# MCU.net
KiCad netlist of a schematic drawn in Altium Designer
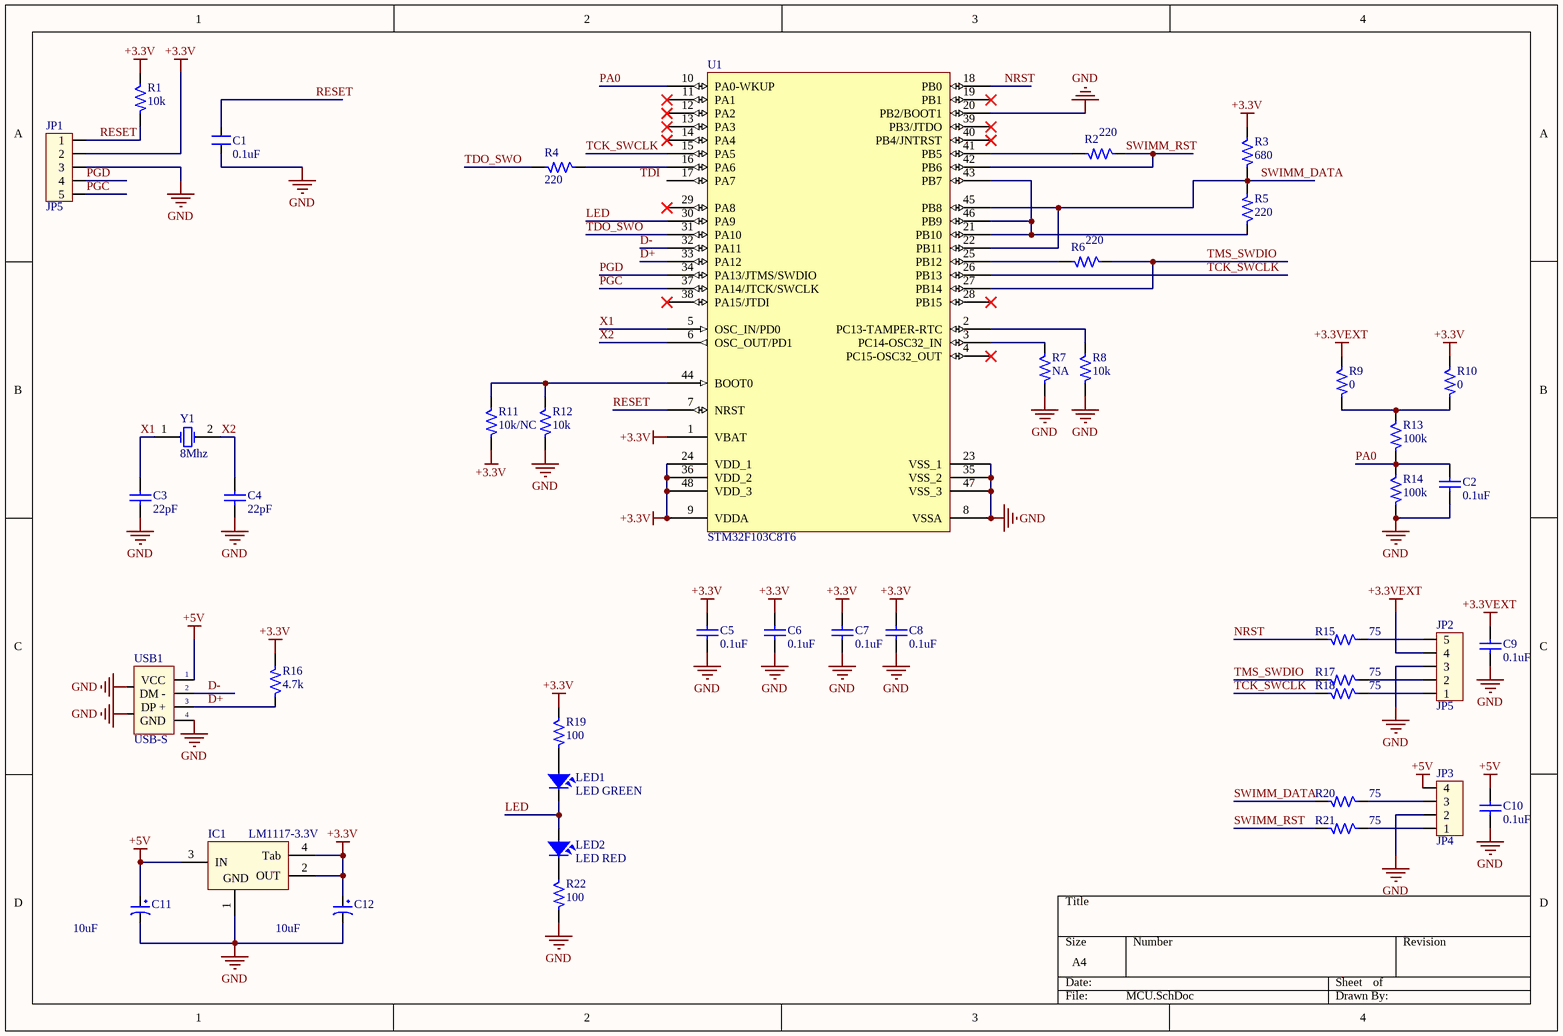
[diagram p0: MCU.SchDoc]

(export (version "E")
  (design (tool "Eeschema 10.0.6"))
  (components
    (comp (ref "C1")
      (value "0.1uF")
      (footprint "C0603")
      (description "Cremic For Xtal 1pF => 100pF")
      (libsource (lib "nl") (part "CAP"))
    )
    (comp (ref "C2")
      (value "0.1uF")
      (footprint "C0603")
      (description "Capacitor (Semiconductor SIM Model)")
      (fields (field (name "PUBLISHER") "Altium Limited"))
      (libsource (lib "VNSKILLS2014-ASM") (part "Cap Semi"))
    )
    (comp (ref "C3")
      (value "22pF")
      (footprint "C0603")
      (description "Capacitor (Semiconductor SIM Model)")
      (fields (field (name "Comment") "0.1uF") (field (name "PUBLISHER") "Altium Limited"))
      (libsource (lib "VNSKILLS2014-ASM") (part "Cap Semi"))
    )
    (comp (ref "C4")
      (value "22pF")
      (footprint "C0603")
      (description "Capacitor (Semiconductor SIM Model)")
      (fields (field (name "Comment") "0.1uF") (field (name "PUBLISHER") "Altium Limited"))
      (libsource (lib "VNSKILLS2014-ASM") (part "Cap Semi"))
    )
    (comp (ref "C5")
      (value "0.1uF")
      (footprint "C0603")
      (description "Capacitor (Semiconductor SIM Model)")
      (fields (field (name "PUBLISHER") "Altium Limited"))
      (libsource (lib "VNSKILLS2014-ASM") (part "Cap Semi"))
    )
    (comp (ref "C6")
      (value "0.1uF")
      (footprint "C0603")
      (description "Capacitor (Semiconductor SIM Model)")
      (fields (field (name "PUBLISHER") "Altium Limited"))
      (libsource (lib "VNSKILLS2014-ASM") (part "Cap Semi"))
    )
    (comp (ref "C7")
      (value "0.1uF")
      (footprint "C0603")
      (description "Capacitor (Semiconductor SIM Model)")
      (fields (field (name "PUBLISHER") "Altium Limited"))
      (libsource (lib "VNSKILLS2014-ASM") (part "Cap Semi"))
    )
    (comp (ref "C8")
      (value "0.1uF")
      (footprint "C0603")
      (description "Capacitor (Semiconductor SIM Model)")
      (fields (field (name "PUBLISHER") "Altium Limited"))
      (libsource (lib "VNSKILLS2014-ASM") (part "Cap Semi"))
    )
    (comp (ref "C9")
      (value "0.1uF")
      (footprint "C0603")
      (description "Capacitor (Semiconductor SIM Model)")
      (fields (field (name "PUBLISHER") "Altium Limited"))
      (libsource (lib "VNSKILLS2014-ASM") (part "Cap Semi"))
    )
    (comp (ref "C10")
      (value "0.1uF")
      (footprint "C0603")
      (description "Capacitor (Semiconductor SIM Model)")
      (fields (field (name "PUBLISHER") "Altium Limited"))
      (libsource (lib "VNSKILLS2014-ASM") (part "Cap Semi"))
    )
    (comp (ref "C11")
      (value "10uF")
      (footprint "C1812")
      (description "Cap P  0,1uF < 22uF , 16 - 50V")
      (libsource (lib "nl") (part "CP1"))
    )
    (comp (ref "C12")
      (value "10uF")
      (footprint "C1812")
      (description "Cap P  0,1uF < 22uF , 16 - 50V")
      (libsource (lib "nl") (part "CP1"))
    )
    (comp (ref "IC1")
      (value "LM1117-3.3V")
      (footprint "SOT223-4N")
      (description "3v3")
      (libsource (lib "syhaunguyen") (part "LM1117"))
    )
    (comp (ref "JP1")
      (value "JP5")
      (footprint "CON5")
      (description "Connector 5")
      (libsource (lib "nl") (part "Con5"))
    )
    (comp (ref "JP2")
      (value "JP5")
      (footprint "CON5")
      (description "Connector 5")
      (libsource (lib "") (part "Con5_1"))
    )
    (comp (ref "JP3")
      (value "JP4")
      (footprint "CON4")
      (description "Connector 4")
      (libsource (lib "nl") (part "Con4"))
    )
    (comp (ref "LED1")
      (value "LED GREEN")
      (footprint "LED0603")
      (description "LED Single colour Green and Red")
      (libsource (lib "nl") (part "LED"))
    )
    (comp (ref "LED2")
      (value "LED RED")
      (footprint "LED0603")
      (description "LED Single colour Green and Red")
      (libsource (lib "nl") (part "LED"))
    )
    (comp (ref "R1")
      (value "10k")
      (footprint "R0603")
      (description "Resistor 1/4W")
      (libsource (lib "nl") (part "R"))
    )
    (comp (ref "R2")
      (value "220")
      (footprint "R0603")
      (description "Resistor 1/4W")
      (libsource (lib "nl") (part "R"))
    )
    (comp (ref "R3")
      (value "680")
      (footprint "R0603")
      (description "Resistor 1/4W")
      (libsource (lib "nl") (part "R"))
    )
    (comp (ref "R4")
      (value "220")
      (footprint "R0603")
      (description "Resistor 1/4W")
      (libsource (lib "nl") (part "R"))
    )
    (comp (ref "R5")
      (value "220")
      (footprint "R0603")
      (description "Resistor 1/4W")
      (libsource (lib "nl") (part "R"))
    )
    (comp (ref "R6")
      (value "220")
      (footprint "R0603")
      (description "Resistor 1/4W")
      (libsource (lib "nl") (part "R"))
    )
    (comp (ref "R7")
      (value "NA")
      (footprint "R0603")
      (description "Resistor 1/4W")
      (libsource (lib "nl") (part "R"))
    )
    (comp (ref "R8")
      (value "10k")
      (footprint "R0603")
      (description "Resistor 1/4W")
      (libsource (lib "nl") (part "R"))
    )
    (comp (ref "R9")
      (value "0")
      (footprint "R0603")
      (description "Resistor 1/4W")
      (libsource (lib "nl") (part "R"))
    )
    (comp (ref "R10")
      (value "0")
      (footprint "R0603")
      (description "Resistor 1/4W")
      (libsource (lib "nl") (part "R"))
    )
    (comp (ref "R11")
      (value "10k/NC")
      (footprint "R0603")
      (description "Resistor 1/4W")
      (libsource (lib "nl") (part "R"))
    )
    (comp (ref "R12")
      (value "10k")
      (footprint "R0603")
      (description "Resistor 1/4W")
      (libsource (lib "nl") (part "R"))
    )
    (comp (ref "R13")
      (value "100k")
      (footprint "R0603")
      (description "Resistor 1/4W")
      (libsource (lib "nl") (part "R"))
    )
    (comp (ref "R14")
      (value "100k")
      (footprint "R0603")
      (description "Resistor 1/4W")
      (libsource (lib "nl") (part "R"))
    )
    (comp (ref "R15")
      (value "75")
      (footprint "R0603")
      (description "Resistor 1/4W")
      (libsource (lib "nl") (part "R"))
    )
    (comp (ref "R16")
      (value "4.7k")
      (footprint "R0603")
      (description "Resistor 1/4W")
      (libsource (lib "nl") (part "R"))
    )
    (comp (ref "R17")
      (value "75")
      (footprint "R0603")
      (description "Resistor 1/4W")
      (libsource (lib "nl") (part "R"))
    )
    (comp (ref "R18")
      (value "75")
      (footprint "R0603")
      (description "Resistor 1/4W")
      (libsource (lib "nl") (part "R"))
    )
    (comp (ref "R19")
      (value "100")
      (footprint "R0603")
      (description "Resistor 1/4W")
      (libsource (lib "nl") (part "R"))
    )
    (comp (ref "R20")
      (value "75")
      (footprint "R0603")
      (description "Resistor 1/4W")
      (libsource (lib "nl") (part "R"))
    )
    (comp (ref "R21")
      (value "75")
      (footprint "R0603")
      (description "Resistor 1/4W")
      (libsource (lib "nl") (part "R"))
    )
    (comp (ref "R22")
      (value "100")
      (footprint "R0603")
      (description "Resistor 1/4W")
      (libsource (lib "nl") (part "R"))
    )
    (comp (ref "U1")
      (value "STM32F103C8T6")
      (footprint "LQFP48_L")
      (description "STM32 ARM-based 32-bit MCU with 64 Kbytes Flash, 48-pin LQFP, Industrial Temperature")
      (fields (field (name "PUBLISHER") "Altium Limited"))
      (libsource (lib "ST Microcontroller 32-Bit STM32") (part "STM32F103C8T6"))
    )
    (comp (ref "USB1")
      (value "USB-S")
      (footprint "USB-S")
      (description "USB connector")
      (libsource (lib "syhaunguyen") (part "USB_S"))
    )
    (comp (ref "Y1")
      (value "8Mhz")
      (footprint "XTA")
      (description "Crystal Oscillator")
      (fields (field (name "PUBLISHER") "Altium Limited"))
      (libsource (lib "Miscellaneous Devices") (part "XTAL"))
    )
  )
  (nets
    (net (code "1") (name "+3.3V") (class "Default")
      (node (ref "C12") (pin "1") (pinfunction "1_1") (pintype "passive"))
      (node (ref "C5") (pin "2") (pinfunction "2_2") (pintype "passive"))
      (node (ref "C6") (pin "2") (pinfunction "2_2") (pintype "passive"))
      (node (ref "C7") (pin "2") (pinfunction "2_2") (pintype "passive"))
      (node (ref "C8") (pin "2") (pinfunction "2_2") (pintype "passive"))
      (node (ref "IC1") (pin "2") (pinfunction "OUT_2") (pintype "passive"))
      (node (ref "IC1") (pin "4") (pinfunction "Tab_4") (pintype "passive"))
      (node (ref "JP1") (pin "2") (pinfunction "2_2") (pintype "passive"))
      (node (ref "R1") (pin "1") (pinfunction "1_1") (pintype "passive"))
      (node (ref "R10") (pin "1") (pinfunction "1_1") (pintype "passive"))
      (node (ref "R11") (pin "2") (pinfunction "2_2") (pintype "passive"))
      (node (ref "R16") (pin "2") (pinfunction "2_2") (pintype "passive"))
      (node (ref "R19") (pin "1") (pinfunction "1_1") (pintype "passive"))
      (node (ref "R3") (pin "1") (pinfunction "1_1") (pintype "passive"))
      (node (ref "U1") (pin "1") (pinfunction "VBAT_1") (pintype "power_in"))
      (node (ref "U1") (pin "24") (pinfunction "VDD_1_24") (pintype "power_in"))
      (node (ref "U1") (pin "36") (pinfunction "VDD_2_36") (pintype "power_in"))
      (node (ref "U1") (pin "48") (pinfunction "VDD_3_48") (pintype "power_in"))
      (node (ref "U1") (pin "9") (pinfunction "VDDA_9") (pintype "power_in"))
    )
    (net (code "2") (name "+3.3VEXT") (class "Default")
      (node (ref "C9") (pin "2") (pinfunction "2_2") (pintype "passive"))
      (node (ref "JP2") (pin "4") (pinfunction "4_4") (pintype "passive"))
      (node (ref "R9") (pin "1") (pinfunction "1_1") (pintype "passive"))
    )
    (net (code "3") (name "+5V") (class "Default")
      (node (ref "C10") (pin "2") (pinfunction "2_2") (pintype "passive"))
      (node (ref "C11") (pin "1") (pinfunction "1_1") (pintype "passive"))
      (node (ref "IC1") (pin "3") (pinfunction "IN_3") (pintype "passive"))
      (node (ref "JP3") (pin "4") (pinfunction "4_4") (pintype "passive"))
      (node (ref "USB1") (pin "1") (pinfunction "VCC_1") (pintype "passive"))
    )
    (net (code "4") (name "/D+") (class "Default")
      (node (ref "R16") (pin "1") (pinfunction "1_1") (pintype "passive"))
      (node (ref "U1") (pin "33") (pinfunction "PA12_33") (pintype "bidirectional"))
      (node (ref "USB1") (pin "3") (pinfunction "DP_+_3") (pintype "passive"))
    )
    (net (code "5") (name "/D-") (class "Default")
      (node (ref "U1") (pin "32") (pinfunction "PA11_32") (pintype "bidirectional"))
      (node (ref "USB1") (pin "2") (pinfunction "DM_-_2") (pintype "passive"))
    )
    (net (code "6") (name "/LED") (class "Default")
      (node (ref "LED1") (pin "2") (pinfunction "2_2") (pintype "passive"))
      (node (ref "LED2") (pin "1") (pinfunction "1_1") (pintype "passive"))
      (node (ref "U1") (pin "30") (pinfunction "PA9_30") (pintype "bidirectional"))
    )
    (net (code "7") (name "/NRST") (class "Default")
      (node (ref "R15") (pin "2") (pinfunction "2_2") (pintype "passive"))
      (node (ref "U1") (pin "18") (pinfunction "PB0_18") (pintype "bidirectional"))
    )
    (net (code "8") (name "/PA0") (class "Default")
      (node (ref "C2") (pin "2") (pinfunction "2_2") (pintype "passive"))
      (node (ref "R13") (pin "2") (pinfunction "2_2") (pintype "passive"))
      (node (ref "R14") (pin "1") (pinfunction "1_1") (pintype "passive"))
      (node (ref "U1") (pin "10") (pinfunction "PA0-WKUP_10") (pintype "bidirectional"))
    )
    (net (code "9") (name "/PGC") (class "Default")
      (node (ref "JP1") (pin "5") (pinfunction "5_5") (pintype "passive"))
      (node (ref "U1") (pin "37") (pinfunction "PA14/JTCK/SWCLK_37") (pintype "bidirectional"))
    )
    (net (code "10") (name "/PGD") (class "Default")
      (node (ref "JP1") (pin "4") (pinfunction "4_4") (pintype "passive"))
      (node (ref "U1") (pin "34") (pinfunction "PA13/JTMS/SWDIO_34") (pintype "bidirectional"))
    )
    (net (code "11") (name "/RESET") (class "Default")
      (node (ref "C1") (pin "2") (pinfunction "2_2") (pintype "passive"))
      (node (ref "JP1") (pin "1") (pinfunction "1_1") (pintype "passive"))
      (node (ref "R1") (pin "2") (pinfunction "2_2") (pintype "passive"))
      (node (ref "U1") (pin "7") (pinfunction "NRST_7") (pintype "bidirectional"))
    )
    (net (code "12") (name "/SWIMM_DATA") (class "Default")
      (node (ref "R20") (pin "2") (pinfunction "2_2") (pintype "passive"))
      (node (ref "R3") (pin "2") (pinfunction "2_2") (pintype "passive"))
      (node (ref "R5") (pin "2") (pinfunction "2_2") (pintype "passive"))
      (node (ref "U1") (pin "22") (pinfunction "PB11_22") (pintype "bidirectional"))
      (node (ref "U1") (pin "45") (pinfunction "PB8_45") (pintype "bidirectional"))
    )
    (net (code "13") (name "/SWIMM_RST") (class "Default")
      (node (ref "R2") (pin "1") (pinfunction "1_1") (pintype "passive"))
      (node (ref "R21") (pin "2") (pinfunction "2_2") (pintype "passive"))
      (node (ref "U1") (pin "42") (pinfunction "PB6_42") (pintype "bidirectional"))
    )
    (net (code "14") (name "/TCK_SWCLK") (class "Default")
      (node (ref "R18") (pin "2") (pinfunction "2_2") (pintype "passive"))
      (node (ref "U1") (pin "15") (pinfunction "PA5_15") (pintype "bidirectional"))
      (node (ref "U1") (pin "26") (pinfunction "PB13_26") (pintype "bidirectional"))
    )
    (net (code "16") (name "/TDO_SWO") (class "Default")
      (node (ref "R4") (pin "2") (pinfunction "2_2") (pintype "passive"))
      (node (ref "U1") (pin "31") (pinfunction "PA10_31") (pintype "bidirectional"))
    )
    (net (code "17") (name "/TMS_SWDIO") (class "Default")
      (node (ref "R17") (pin "2") (pinfunction "2_2") (pintype "passive"))
      (node (ref "R6") (pin "1") (pinfunction "1_1") (pintype "passive"))
      (node (ref "U1") (pin "27") (pinfunction "PB14_27") (pintype "bidirectional"))
    )
    (net (code "18") (name "/X1") (class "Default")
      (node (ref "C3") (pin "2") (pinfunction "2_2") (pintype "passive"))
      (node (ref "U1") (pin "5") (pinfunction "OSC_IN/PD0_5") (pintype "input"))
      (node (ref "Y1") (pin "1") (pinfunction "OSC1_1") (pintype "passive"))
    )
    (net (code "19") (name "/X2") (class "Default")
      (node (ref "C4") (pin "2") (pinfunction "2_2") (pintype "passive"))
      (node (ref "U1") (pin "6") (pinfunction "OSC_OUT/PD1_6") (pintype "output"))
      (node (ref "Y1") (pin "2") (pinfunction "OSC2_2") (pintype "passive"))
    )
    (net (code "20") (name "GND") (class "Default")
      (node (ref "C1") (pin "1") (pinfunction "1_1") (pintype "passive"))
      (node (ref "C10") (pin "1") (pinfunction "1_1") (pintype "passive"))
      (node (ref "C11") (pin "2") (pinfunction "2_2") (pintype "passive"))
      (node (ref "C12") (pin "2") (pinfunction "2_2") (pintype "passive"))
      (node (ref "C2") (pin "1") (pinfunction "1_1") (pintype "passive"))
      (node (ref "C3") (pin "1") (pinfunction "1_1") (pintype "passive"))
      (node (ref "C4") (pin "1") (pinfunction "1_1") (pintype "passive"))
      (node (ref "C5") (pin "1") (pinfunction "1_1") (pintype "passive"))
      (node (ref "C6") (pin "1") (pinfunction "1_1") (pintype "passive"))
      (node (ref "C7") (pin "1") (pinfunction "1_1") (pintype "passive"))
      (node (ref "C8") (pin "1") (pinfunction "1_1") (pintype "passive"))
      (node (ref "C9") (pin "1") (pinfunction "1_1") (pintype "passive"))
      (node (ref "IC1") (pin "1") (pinfunction "ADJ/G_1") (pintype "passive"))
      (node (ref "JP1") (pin "3") (pinfunction "3_3") (pintype "passive"))
      (node (ref "JP2") (pin "3") (pinfunction "3_3") (pintype "passive"))
      (node (ref "JP3") (pin "2") (pinfunction "2_2") (pintype "passive"))
      (node (ref "R12") (pin "2") (pinfunction "2_2") (pintype "passive"))
      (node (ref "R14") (pin "2") (pinfunction "2_2") (pintype "passive"))
      (node (ref "R22") (pin "2") (pinfunction "2_2") (pintype "passive"))
      (node (ref "R7") (pin "2") (pinfunction "2_2") (pintype "passive"))
      (node (ref "R8") (pin "2") (pinfunction "2_2") (pintype "passive"))
      (node (ref "U1") (pin "20") (pinfunction "PB2/BOOT1_20") (pintype "bidirectional"))
      (node (ref "U1") (pin "23") (pinfunction "VSS_1_23") (pintype "power_in"))
      (node (ref "U1") (pin "35") (pinfunction "VSS_2_35") (pintype "power_in"))
      (node (ref "U1") (pin "47") (pinfunction "VSS_3_47") (pintype "power_in"))
      (node (ref "U1") (pin "8") (pinfunction "VSSA_8") (pintype "power_in"))
      (node (ref "USB1") (pin "4") (pinfunction "GND_4") (pintype "passive"))
      (node (ref "USB1") (pin "5") (pinfunction "5_5") (pintype "passive"))
      (node (ref "USB1") (pin "6") (pinfunction "6_6") (pintype "passive"))
    )
    (net (code "21") (name "Net-(JP2-Pad1)") (class "Default")
      (node (ref "JP2") (pin "1") (pinfunction "1_1") (pintype "passive"))
      (node (ref "R18") (pin "1") (pinfunction "1_1") (pintype "passive"))
    )
    (net (code "22") (name "Net-(JP2-Pad2)") (class "Default")
      (node (ref "JP2") (pin "2") (pinfunction "2_2") (pintype "passive"))
      (node (ref "R17") (pin "1") (pinfunction "1_1") (pintype "passive"))
    )
    (net (code "23") (name "Net-(JP2-Pad5)") (class "Default")
      (node (ref "JP2") (pin "5") (pinfunction "5_5") (pintype "passive"))
      (node (ref "R15") (pin "1") (pinfunction "1_1") (pintype "passive"))
    )
    (net (code "24") (name "Net-(JP3-Pad1)") (class "Default")
      (node (ref "JP3") (pin "1") (pinfunction "1_1") (pintype "passive"))
      (node (ref "R21") (pin "1") (pinfunction "1_1") (pintype "passive"))
    )
    (net (code "25") (name "Net-(JP3-Pad3)") (class "Default")
      (node (ref "JP3") (pin "3") (pinfunction "3_3") (pintype "passive"))
      (node (ref "R20") (pin "1") (pinfunction "1_1") (pintype "passive"))
    )
    (net (code "26") (name "Net-(LED1-Pad1)") (class "Default")
      (node (ref "LED1") (pin "1") (pinfunction "1_1") (pintype "passive"))
      (node (ref "R19") (pin "2") (pinfunction "2_2") (pintype "passive"))
    )
    (net (code "27") (name "Net-(LED2-Pad2)") (class "Default")
      (node (ref "LED2") (pin "2") (pinfunction "2_2") (pintype "passive"))
      (node (ref "R22") (pin "1") (pinfunction "1_1") (pintype "passive"))
    )
    (net (code "28") (name "Net-(R10-Pad2)") (class "Default")
      (node (ref "R10") (pin "2") (pinfunction "2_2") (pintype "passive"))
      (node (ref "R13") (pin "1") (pinfunction "1_1") (pintype "passive"))
      (node (ref "R9") (pin "2") (pinfunction "2_2") (pintype "passive"))
    )
    (net (code "29") (name "Net-(U1-BOOT0)") (class "Default")
      (node (ref "R11") (pin "1") (pinfunction "1_1") (pintype "passive"))
      (node (ref "R12") (pin "1") (pinfunction "1_1") (pintype "passive"))
      (node (ref "U1") (pin "44") (pinfunction "BOOT0_44") (pintype "input"))
    )
    (net (code "30") (name "Net-(U1-PA6)") (class "Default")
      (node (ref "R4") (pin "1") (pinfunction "1_1") (pintype "passive"))
      (node (ref "U1") (pin "16") (pinfunction "PA6_16") (pintype "bidirectional"))
    )
    (net (code "31") (name "Net-(U1-PB5)") (class "Default")
      (node (ref "R2") (pin "2") (pinfunction "2_2") (pintype "passive"))
      (node (ref "U1") (pin "41") (pinfunction "PB5_41") (pintype "bidirectional"))
    )
    (net (code "32") (name "Net-(U1-PB10)") (class "Default")
      (node (ref "R5") (pin "1") (pinfunction "1_1") (pintype "passive"))
      (node (ref "U1") (pin "21") (pinfunction "PB10_21") (pintype "bidirectional"))
      (node (ref "U1") (pin "43") (pinfunction "PB7_43") (pintype "bidirectional"))
      (node (ref "U1") (pin "46") (pinfunction "PB9_46") (pintype "bidirectional"))
    )
    (net (code "33") (name "Net-(U1-PB12)") (class "Default")
      (node (ref "R6") (pin "2") (pinfunction "2_2") (pintype "passive"))
      (node (ref "U1") (pin "25") (pinfunction "PB12_25") (pintype "bidirectional"))
    )
    (net (code "34") (name "Net-(U1-PC13-TAMPER-RTC)") (class "Default")
      (node (ref "R8") (pin "1") (pinfunction "1_1") (pintype "passive"))
      (node (ref "U1") (pin "2") (pinfunction "PC13-TAMPER-RTC_2") (pintype "bidirectional"))
    )
    (net (code "35") (name "Net-(U1-PC14-OSC32_IN)") (class "Default")
      (node (ref "R7") (pin "1") (pinfunction "1_1") (pintype "passive"))
      (node (ref "U1") (pin "3") (pinfunction "PC14-OSC32_IN_3") (pintype "bidirectional"))
    )
    (net (code "36") (name "unconnected-(U1-PA1-Pad11)") (class "Default")
      (node (ref "U1") (pin "11") (pinfunction "PA1_11") (pintype "bidirectional+no_connect"))
    )
    (net (code "37") (name "unconnected-(U1-PA2-Pad12)") (class "Default")
      (node (ref "U1") (pin "12") (pinfunction "PA2_12") (pintype "bidirectional+no_connect"))
    )
    (net (code "38") (name "unconnected-(U1-PA3-Pad13)") (class "Default")
      (node (ref "U1") (pin "13") (pinfunction "PA3_13") (pintype "bidirectional+no_connect"))
    )
    (net (code "39") (name "unconnected-(U1-PA4-Pad14)") (class "Default")
      (node (ref "U1") (pin "14") (pinfunction "PA4_14") (pintype "bidirectional+no_connect"))
    )
    (net (code "40") (name "unconnected-(U1-PA7-Pad17)") (class "Default")
      (node (ref "U1") (pin "17") (pinfunction "PA7_17") (pintype "bidirectional"))
    )
    (net (code "41") (name "unconnected-(U1-PA8-Pad29)") (class "Default")
      (node (ref "U1") (pin "29") (pinfunction "PA8_29") (pintype "bidirectional+no_connect"))
    )
    (net (code "42") (name "unconnected-(U1-PA15{slash}JTDI-Pad38)") (class "Default")
      (node (ref "U1") (pin "38") (pinfunction "PA15/JTDI_38") (pintype "bidirectional+no_connect"))
    )
    (net (code "43") (name "unconnected-(U1-PB1-Pad19)") (class "Default")
      (node (ref "U1") (pin "19") (pinfunction "PB1_19") (pintype "bidirectional+no_connect"))
    )
    (net (code "44") (name "unconnected-(U1-PB3{slash}JTDO-Pad39)") (class "Default")
      (node (ref "U1") (pin "39") (pinfunction "PB3/JTDO_39") (pintype "bidirectional+no_connect"))
    )
    (net (code "45") (name "unconnected-(U1-PB4{slash}JNTRST-Pad40)") (class "Default")
      (node (ref "U1") (pin "40") (pinfunction "PB4/JNTRST_40") (pintype "bidirectional+no_connect"))
    )
    (net (code "46") (name "unconnected-(U1-PB15-Pad28)") (class "Default")
      (node (ref "U1") (pin "28") (pinfunction "PB15_28") (pintype "bidirectional+no_connect"))
    )
    (net (code "47") (name "unconnected-(U1-PC15-OSC32_OUT-Pad4)") (class "Default")
      (node (ref "U1") (pin "4") (pinfunction "PC15-OSC32_OUT_4") (pintype "bidirectional+no_connect"))
    )
  )
)
